# BLT_Preliminary_Avionics_Schematic_Brand.net
KiCad netlist of a schematic drawn in EAGLE
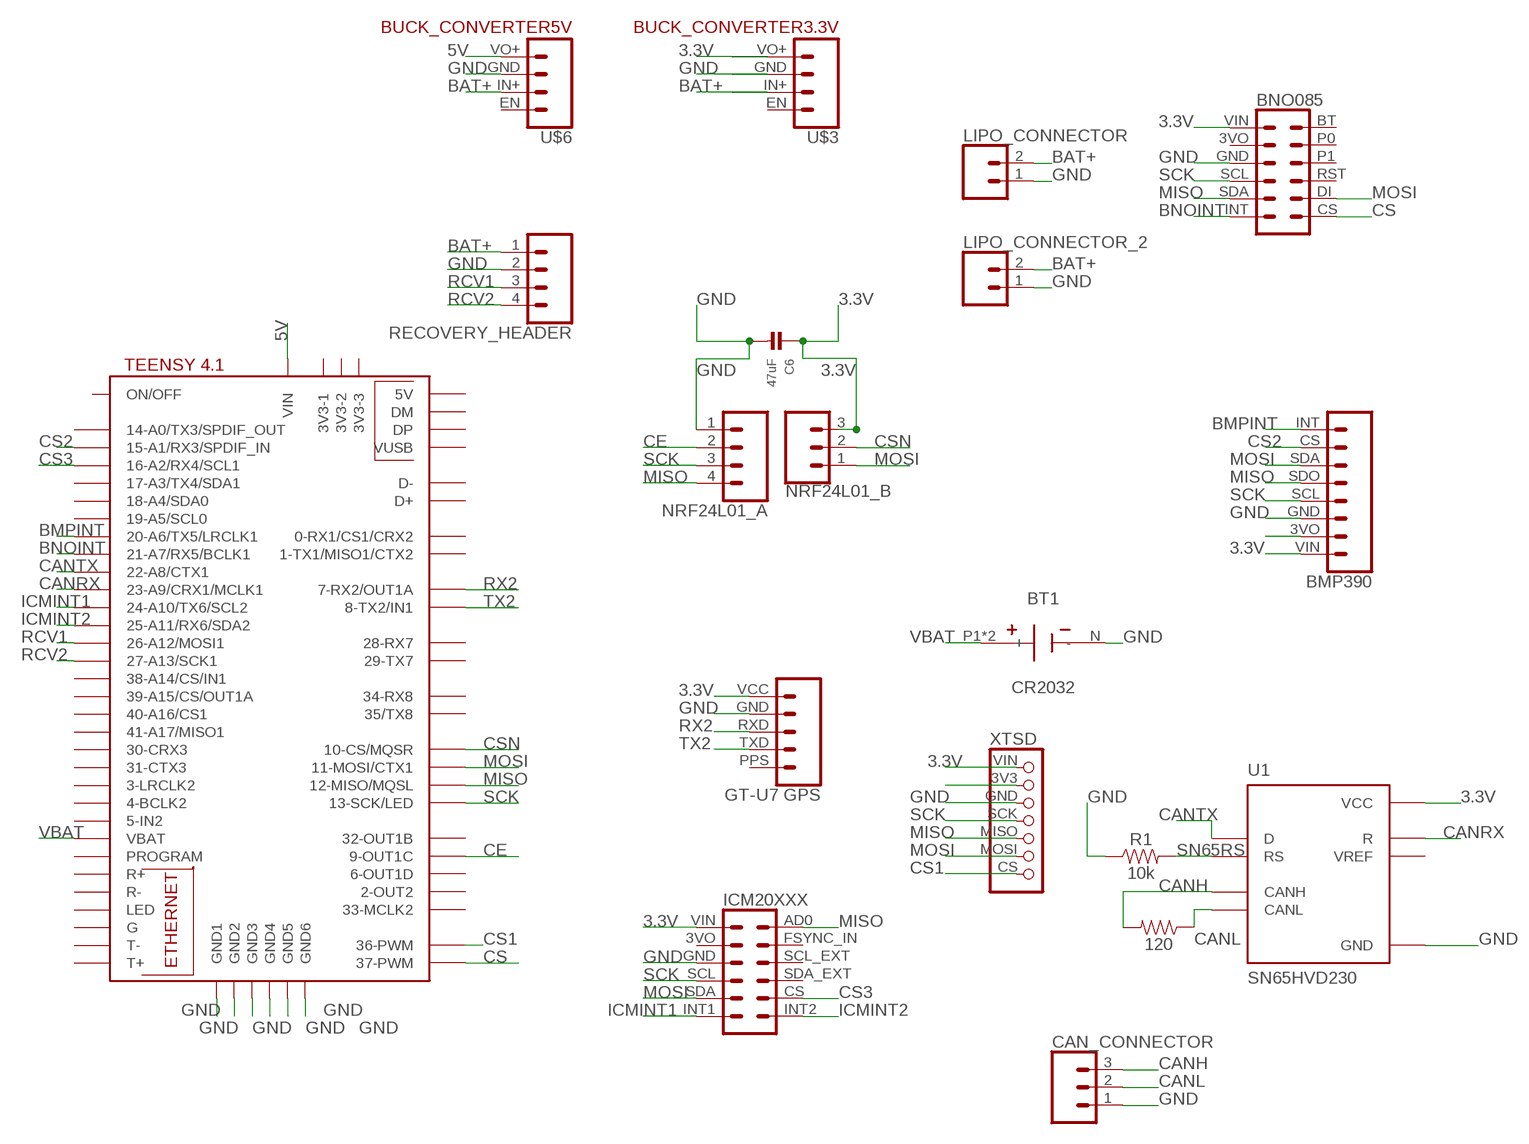
[diagram p0: schematic, sheet 1]

(export (version "E")
  (design (tool "Eeschema 10.0.6"))
  (components
    (comp (ref "120")
      (value "RESISTOR1206")
      (footprint "eagle-import:1206")
      (libsource (lib "eagle-import") (part "RESISTOR1206"))
    )
    (comp (ref "BT1")
      (value "CR2032")
      (footprint "eagle-import:BAT_3003")
      (fields (field (name "MANUFACTURER") "Keystone Electronics") (field (name "MPN") "3003"))
      (libsource (lib "eagle-import") (part "COIN-CELL-THM-3P?--3003CR2032"))
    )
    (comp (ref "C6")
      (value "47uF")
      (footprint "eagle-import:0805")
      (libsource (lib "eagle-import") (part "CAP_CERAMIC0805"))
    )
    (comp (ref "CAN_CONNECTOR")
      (value "CONN_03")
      (footprint "eagle-import:1X03")
      (libsource (lib "eagle-import") (part "CONN_03"))
    )
    (comp (ref "LIPO_CONNECTOR")
      (value "CONN_02PTH4")
      (footprint "eagle-import:1X02_XTRA_BIG")
      (libsource (lib "eagle-import") (part "CONN_02PTH4"))
    )
    (comp (ref "LIPO_CONNECTOR_2")
      (value "CONN_02")
      (footprint "eagle-import:1X02")
      (libsource (lib "eagle-import") (part "CONN_02"))
    )
    (comp (ref "NRF24L01_A")
      (value "CONN_04")
      (footprint "eagle-import:1X04")
      (libsource (lib "eagle-import") (part "CONN_04"))
    )
    (comp (ref "NRF24L01_B")
      (value "CONN_03")
      (footprint "eagle-import:1X03")
      (libsource (lib "eagle-import") (part "CONN_03"))
    )
    (comp (ref "R1")
      (value "10k")
      (footprint "eagle-import:0603")
      (libsource (lib "eagle-import") (part "10KOHM-0603-1/10W-1%"))
    )
    (comp (ref "RECOVERY_HEADER")
      (value "CONN_04")
      (footprint "eagle-import:1X04")
      (libsource (lib "eagle-import") (part "CONN_04"))
    )
    (comp (ref "U$1")
      (value "TEENSY41")
      (footprint "eagle-import:TEENSY41")
      (libsource (lib "eagle-import") (part "TEENSY41"))
    )
    (comp (ref "U$2")
      (value "BMP390")
      (footprint "eagle-import:MICROBUILDER_1X08_ROUND")
      (libsource (lib "eagle-import") (part "BMP390"))
    )
    (comp (ref "U$3")
      (value "BUCK_CONVERTER3.3V")
      (footprint "eagle-import:1X04")
      (fields (field (name "VOLTAGE") "3.3V"))
      (libsource (lib "eagle-import") (part "BUCK_CONVERTER3.3V"))
    )
    (comp (ref "U$4")
      (value "GT-U7_GPS")
      (footprint "eagle-import:1X05")
      (libsource (lib "eagle-import") (part "GT-U7_GPS"))
    )
    (comp (ref "U$5")
      (value "XTSDXTSD_PINS")
      (footprint "eagle-import:1X07")
      (libsource (lib "eagle-import") (part "XTSDXTSD_PINS"))
    )
    (comp (ref "U$6")
      (value "BUCK_CONVERTER5V")
      (footprint "eagle-import:1X04")
      (fields (field (name "VOLTAGE") "5V"))
      (libsource (lib "eagle-import") (part "BUCK_CONVERTER5V"))
    )
    (comp (ref "U$7")
      (value "BNO085")
      (footprint "eagle-import:MICROBUILDER_1X06_ROUND_70")
      (libsource (lib "eagle-import") (part "BNO085"))
    )
    (comp (ref "U$8")
      (value "ICM20XXX")
      (footprint "eagle-import:1X06")
      (libsource (lib "eagle-import") (part "ICM20XXX"))
    )
    (comp (ref "U1")
      (value "SN65HVD230")
      (footprint "eagle-import:SOIC127P599X175-8N")
      (fields (field (name "MF") "Texas Instruments"))
      (libsource (lib "eagle-import") (part "SN65HVD230"))
    )
  )
  (nets
    (net (code "1") (name "/3.3V") (class "Default")
      (node (ref "C6") (pin "1") (pinfunction "P$1_1") (pintype "passive"))
      (node (ref "NRF24L01_B") (pin "3") (pinfunction "3_3") (pintype "passive"))
      (node (ref "U$2") (pin "VIN") (pinfunction "VIN_VIN") (pintype "passive"))
      (node (ref "U$3") (pin "VO+") (pinfunction "VO+_VO+") (pintype "passive"))
      (node (ref "U$4") (pin "VCC") (pinfunction "VCC_VCC") (pintype "passive"))
      (node (ref "U$5") (pin "VIN") (pinfunction "VIN_VIN") (pintype "passive"))
      (node (ref "U$7") (pin "VIN") (pinfunction "VIN_VIN") (pintype "passive"))
      (node (ref "U$8") (pin "VIN") (pinfunction "VCC_VIN") (pintype "passive"))
      (node (ref "U1") (pin "3") (pinfunction "VCC_3") (pintype "power_in"))
    )
    (net (code "2") (name "/5V") (class "Default")
      (node (ref "U$1") (pin "VIN") (pinfunction "VIN_VIN") (pintype "bidirectional"))
      (node (ref "U$6") (pin "VO+") (pinfunction "VO+_VO+") (pintype "passive"))
    )
    (net (code "3") (name "/BAT+") (class "Default")
      (node (ref "LIPO_CONNECTOR") (pin "2") (pinfunction "2_2") (pintype "passive"))
      (node (ref "LIPO_CONNECTOR_2") (pin "2") (pinfunction "2_2") (pintype "passive"))
      (node (ref "RECOVERY_HEADER") (pin "1") (pinfunction "1_1") (pintype "passive"))
      (node (ref "U$3") (pin "IN+") (pinfunction "IN+_IN+") (pintype "passive"))
      (node (ref "U$6") (pin "IN+") (pinfunction "IN+_IN+") (pintype "passive"))
    )
    (net (code "4") (name "/BMPINT") (class "Default")
      (node (ref "U$1") (pin "20-A6/TX5/LRCLK1") (pinfunction "20-A6/TX5/LRCLK1_20-A6/TX5/LRCLK1") (pintype "bidirectional"))
      (node (ref "U$2") (pin "INT") (pinfunction "INT_INT") (pintype "passive"))
    )
    (net (code "5") (name "/BNOINT") (class "Default")
      (node (ref "U$1") (pin "21-A7/RX5/BCLK1") (pinfunction "21-A7/RX5/BCLK1_21-A7/RX5/BCLK1") (pintype "bidirectional"))
      (node (ref "U$7") (pin "INT") (pinfunction "INT_INT") (pintype "passive"))
    )
    (net (code "6") (name "/CANH") (class "Default")
      (node (ref "120") (pin "2") (pinfunction "2_2") (pintype "passive"))
      (node (ref "CAN_CONNECTOR") (pin "3") (pinfunction "3_3") (pintype "passive"))
      (node (ref "U1") (pin "7") (pinfunction "CANH_7") (pintype "bidirectional"))
    )
    (net (code "7") (name "/CANL") (class "Default")
      (node (ref "120") (pin "1") (pinfunction "1_1") (pintype "passive"))
      (node (ref "CAN_CONNECTOR") (pin "2") (pinfunction "2_2") (pintype "passive"))
      (node (ref "U1") (pin "6") (pinfunction "CANL_6") (pintype "bidirectional"))
    )
    (net (code "8") (name "/CANRX") (class "Default")
      (node (ref "U$1") (pin "23-A9/CRX1/MCLK1") (pinfunction "23-A9/CRX1/MCLK1_23-A9/CRX1/MCLK1") (pintype "bidirectional"))
      (node (ref "U1") (pin "4") (pinfunction "R_4") (pintype "output"))
    )
    (net (code "9") (name "/CANTX") (class "Default")
      (node (ref "U$1") (pin "22-A8/CTX1") (pinfunction "22-A8/CTX1_22-A8/CTX1") (pintype "bidirectional"))
      (node (ref "U1") (pin "1") (pinfunction "D_1") (pintype "input"))
    )
    (net (code "10") (name "/CE") (class "Default")
      (node (ref "NRF24L01_A") (pin "2") (pinfunction "2_2") (pintype "passive"))
      (node (ref "U$1") (pin "9-OUT1C") (pinfunction "9-OUT1C_9-OUT1C") (pintype "bidirectional"))
    )
    (net (code "11") (name "/CS") (class "Default")
      (node (ref "U$1") (pin "37-PWM") (pinfunction "37-PWM_37-PWM") (pintype "bidirectional"))
      (node (ref "U$7") (pin "CS") (pinfunction "CS_CS") (pintype "passive"))
    )
    (net (code "12") (name "/CS1") (class "Default")
      (node (ref "U$1") (pin "36-PWM") (pinfunction "36-PWM_36-PWM") (pintype "bidirectional"))
      (node (ref "U$5") (pin "CS") (pinfunction "CS_CS") (pintype "passive"))
    )
    (net (code "13") (name "/CS2") (class "Default")
      (node (ref "U$1") (pin "15-A1/RX3/SPDIF_IN") (pinfunction "15-A1/RX3/SPDIF_IN_15-A1/RX3/SPDIF_IN") (pintype "bidirectional"))
      (node (ref "U$2") (pin "CS") (pinfunction "CS_CS") (pintype "passive"))
    )
    (net (code "14") (name "/CS3") (class "Default")
      (node (ref "U$1") (pin "16-A2/RX4/SCL1") (pinfunction "16-A2/RX4/SCL1_16-A2/RX4/SCL1") (pintype "bidirectional"))
      (node (ref "U$8") (pin "CS") (pinfunction "CS_CS") (pintype "passive"))
    )
    (net (code "15") (name "/CSN") (class "Default")
      (node (ref "NRF24L01_B") (pin "2") (pinfunction "2_2") (pintype "passive"))
      (node (ref "U$1") (pin "10-CS\\MQSR") (pinfunction "10-CS/MQSR_10-CS\\MQSR") (pintype "bidirectional"))
    )
    (net (code "16") (name "/GND") (class "Default")
      (node (ref "BT1") (pin "N") (pinfunction "-_N") (pintype "bidirectional"))
      (node (ref "C6") (pin "2") (pinfunction "P$2_2") (pintype "passive"))
      (node (ref "CAN_CONNECTOR") (pin "1") (pinfunction "1_1") (pintype "passive"))
      (node (ref "LIPO_CONNECTOR") (pin "1") (pinfunction "1_1") (pintype "passive"))
      (node (ref "LIPO_CONNECTOR_2") (pin "1") (pinfunction "1_1") (pintype "passive"))
      (node (ref "NRF24L01_A") (pin "1") (pinfunction "1_1") (pintype "passive"))
      (node (ref "R1") (pin "1") (pinfunction "1_1") (pintype "passive"))
      (node (ref "RECOVERY_HEADER") (pin "2") (pinfunction "2_2") (pintype "passive"))
      (node (ref "U$1") (pin "GND1") (pinfunction "GND1_GND1") (pintype "bidirectional"))
      (node (ref "U$1") (pin "GND2") (pinfunction "GND2_GND2") (pintype "bidirectional"))
      (node (ref "U$1") (pin "GND3") (pinfunction "GND3_GND3") (pintype "bidirectional"))
      (node (ref "U$1") (pin "GND4") (pinfunction "GND4_GND4") (pintype "bidirectional"))
      (node (ref "U$1") (pin "GND5") (pinfunction "GND5_GND5") (pintype "bidirectional"))
      (node (ref "U$1") (pin "GND6") (pinfunction "GND6_GND6") (pintype "bidirectional"))
      (node (ref "U$2") (pin "GND") (pinfunction "GND_GND") (pintype "passive"))
      (node (ref "U$3") (pin "GND") (pinfunction "GND_GND") (pintype "passive"))
      (node (ref "U$4") (pin "GND") (pinfunction "GND_GND") (pintype "passive"))
      (node (ref "U$5") (pin "GND") (pinfunction "GND_GND") (pintype "passive"))
      (node (ref "U$6") (pin "GND") (pinfunction "GND_GND") (pintype "passive"))
      (node (ref "U$7") (pin "GND") (pinfunction "GND_GND") (pintype "passive"))
      (node (ref "U$8") (pin "GND") (pinfunction "GND_GND") (pintype "passive"))
      (node (ref "U1") (pin "2") (pinfunction "GND_2") (pintype "power_in"))
    )
    (net (code "17") (name "/ICMINT1") (class "Default")
      (node (ref "U$1") (pin "24-A10/TX6/SCL2") (pinfunction "24-A10/TX6/SCL2_24-A10/TX6/SCL2") (pintype "bidirectional"))
      (node (ref "U$8") (pin "INT1") (pinfunction "INT1_INT1") (pintype "passive"))
    )
    (net (code "18") (name "/ICMINT2") (class "Default")
      (node (ref "U$1") (pin "25-A11/RX6/SDA2") (pinfunction "25-A11/RX6/SDA2_25-A11/RX6/SDA2") (pintype "bidirectional"))
      (node (ref "U$8") (pin "INT2") (pinfunction "INT2_INT2") (pintype "passive"))
    )
    (net (code "19") (name "/MISO") (class "Default")
      (node (ref "NRF24L01_A") (pin "4") (pinfunction "4_4") (pintype "passive"))
      (node (ref "U$1") (pin "12-MISO/MQSL") (pinfunction "12-MISO/MQSL_12-MISO/MQSL") (pintype "bidirectional"))
      (node (ref "U$2") (pin "SDO") (pinfunction "SDO_SDO") (pintype "passive"))
      (node (ref "U$5") (pin "MISO") (pinfunction "MISO_MISO") (pintype "passive"))
      (node (ref "U$7") (pin "SDA") (pinfunction "SDA_SDA") (pintype "passive"))
      (node (ref "U$8") (pin "AD0") (pinfunction "AD0_AD0") (pintype "passive"))
    )
    (net (code "20") (name "/MOSI") (class "Default")
      (node (ref "NRF24L01_B") (pin "1") (pinfunction "1_1") (pintype "passive"))
      (node (ref "U$1") (pin "11-MOSI/CTX1") (pinfunction "11-MOSI/CTX1_11-MOSI/CTX1") (pintype "bidirectional"))
      (node (ref "U$2") (pin "SDA") (pinfunction "SDA_SDA") (pintype "passive"))
      (node (ref "U$5") (pin "MOSI") (pinfunction "MOSI_MOSI") (pintype "passive"))
      (node (ref "U$7") (pin "DI") (pinfunction "DI_DI") (pintype "passive"))
      (node (ref "U$8") (pin "SDA") (pinfunction "SDA_SDA") (pintype "passive"))
    )
    (net (code "21") (name "/RCV1") (class "Default")
      (node (ref "RECOVERY_HEADER") (pin "3") (pinfunction "3_3") (pintype "passive"))
      (node (ref "U$1") (pin "26-A12/MOSI1") (pinfunction "26-A12/MOSI1_26-A12/MOSI1") (pintype "bidirectional"))
    )
    (net (code "22") (name "/RCV2") (class "Default")
      (node (ref "RECOVERY_HEADER") (pin "4") (pinfunction "4_4") (pintype "passive"))
      (node (ref "U$1") (pin "27-A13/SCK1") (pinfunction "27-A13/SCK1_27-A13/SCK1") (pintype "bidirectional"))
    )
    (net (code "23") (name "/RX2") (class "Default")
      (node (ref "U$1") (pin "7-RX2/OUT1A") (pinfunction "7-RX2/OUT1A_7-RX2/OUT1A") (pintype "bidirectional"))
      (node (ref "U$4") (pin "RXD") (pinfunction "RXD_RXD") (pintype "passive"))
    )
    (net (code "24") (name "/SCK") (class "Default")
      (node (ref "NRF24L01_A") (pin "3") (pinfunction "3_3") (pintype "passive"))
      (node (ref "U$1") (pin "13-SCK/LED") (pinfunction "13-SCK/LED_13-SCK/LED") (pintype "bidirectional"))
      (node (ref "U$2") (pin "SCL") (pinfunction "SCL_SCL") (pintype "passive"))
      (node (ref "U$5") (pin "SCK") (pinfunction "SCK_SCK") (pintype "passive"))
      (node (ref "U$7") (pin "SCL") (pinfunction "SCL_SCL") (pintype "passive"))
      (node (ref "U$8") (pin "SCL") (pinfunction "SCL_SCL") (pintype "passive"))
    )
    (net (code "25") (name "/SN65RS") (class "Default")
      (node (ref "R1") (pin "2") (pinfunction "2_2") (pintype "passive"))
      (node (ref "U1") (pin "8") (pinfunction "RS_8") (pintype "input"))
    )
    (net (code "26") (name "/TX2") (class "Default")
      (node (ref "U$1") (pin "8-TX2/IN1") (pinfunction "8-TX2/IN1_8-TX2/IN1") (pintype "bidirectional"))
      (node (ref "U$4") (pin "TXD") (pinfunction "TXD_TXD") (pintype "passive"))
    )
    (net (code "27") (name "/VBAT") (class "Default")
      (node (ref "BT1") (pin "P1") (pinfunction "+_P1") (pintype "bidirectional"))
      (node (ref "BT1") (pin "P2") (pinfunction "+_P2") (pintype "bidirectional"))
      (node (ref "U$1") (pin "VBAT") (pinfunction "VBAT_VBAT") (pintype "bidirectional"))
    )
    (net (code "28") (name "unconnected-(U$1-5V-Pad+5V)") (class "Default")
      (node (ref "U$1") (pin "+5V") (pinfunction "5V_+5V") (pintype "bidirectional"))
    )
    (net (code "29") (name "unconnected-(U$1-35{slash}TX8-Pad35-TX8)") (class "Default")
      (node (ref "U$1") (pin "35-TX8") (pinfunction "35/TX8_35-TX8") (pintype "bidirectional"))
    )
    (net (code "30") (name "unconnected-(U$1-Pad0-RX1{slash}CS1{slash}CRX2)") (class "Default")
      (node (ref "U$1") (pin "0-RX1/CS1/CRX2") (pinfunction "0-RX1/CS1/CRX2_0-RX1/CS1/CRX2") (pintype "bidirectional"))
    )
    (net (code "31") (name "unconnected-(U$1-Pad1-TX1{slash}MISO1{slash}CTX2)") (class "Default")
      (node (ref "U$1") (pin "1-TX1/MISO1/CTX2") (pinfunction "1-TX1/MISO1/CTX2_1-TX1/MISO1/CTX2") (pintype "bidirectional"))
    )
    (net (code "32") (name "unconnected-(U$1-Pad2-OUT2)") (class "Default")
      (node (ref "U$1") (pin "2-OUT2") (pinfunction "2-OUT2_2-OUT2") (pintype "bidirectional"))
    )
    (net (code "33") (name "unconnected-(U$1-Pad3-LRCLK2)") (class "Default")
      (node (ref "U$1") (pin "3-LRCLK2") (pinfunction "3-LRCLK2_3-LRCLK2") (pintype "bidirectional"))
    )
    (net (code "34") (name "unconnected-(U$1-Pad3V3-1)") (class "Default")
      (node (ref "U$1") (pin "3V3-1") (pinfunction "3V3-1_3V3-1") (pintype "bidirectional"))
    )
    (net (code "35") (name "unconnected-(U$1-Pad3V3-2)") (class "Default")
      (node (ref "U$1") (pin "3V3-2") (pinfunction "3V3-2_3V3-2") (pintype "bidirectional"))
    )
    (net (code "36") (name "unconnected-(U$1-Pad3V3-3)") (class "Default")
      (node (ref "U$1") (pin "3V3-3") (pinfunction "3V3-3_3V3-3") (pintype "bidirectional"))
    )
    (net (code "37") (name "unconnected-(U$1-Pad4-BCLK2)") (class "Default")
      (node (ref "U$1") (pin "4-BCLK2") (pinfunction "4-BCLK2_4-BCLK2") (pintype "bidirectional"))
    )
    (net (code "38") (name "unconnected-(U$1-Pad5-IN2)") (class "Default")
      (node (ref "U$1") (pin "5-IN2") (pinfunction "5-IN2_5-IN2") (pintype "bidirectional"))
    )
    (net (code "39") (name "unconnected-(U$1-Pad6-OUT1D)") (class "Default")
      (node (ref "U$1") (pin "6-OUT1D") (pinfunction "6-OUT1D_6-OUT1D") (pintype "bidirectional"))
    )
    (net (code "40") (name "unconnected-(U$1-Pad14-A0{slash}TX3{slash}SPDIF_OUT)") (class "Default")
      (node (ref "U$1") (pin "14-A0/TX3/SPDIF_OUT") (pinfunction "14-A0/TX3/SPDIF_OUT_14-A0/TX3/SPDIF_OUT") (pintype "bidirectional"))
    )
    (net (code "41") (name "unconnected-(U$1-Pad17-A3{slash}TX4{slash}SDA1)") (class "Default")
      (node (ref "U$1") (pin "17-A3/TX4/SDA1") (pinfunction "17-A3/TX4/SDA1_17-A3/TX4/SDA1") (pintype "bidirectional"))
    )
    (net (code "42") (name "unconnected-(U$1-Pad18-A4{slash}SDA0)") (class "Default")
      (node (ref "U$1") (pin "18-A4/SDA0") (pinfunction "18-A4/SDA0_18-A4/SDA0") (pintype "bidirectional"))
    )
    (net (code "43") (name "unconnected-(U$1-Pad19-A5{slash}SCL0)") (class "Default")
      (node (ref "U$1") (pin "19-A5/SCL0") (pinfunction "19-A5/SCL0_19-A5/SCL0") (pintype "bidirectional"))
    )
    (net (code "44") (name "unconnected-(U$1-Pad28-RX7)") (class "Default")
      (node (ref "U$1") (pin "28-RX7") (pinfunction "28-RX7_28-RX7") (pintype "bidirectional"))
    )
    (net (code "45") (name "unconnected-(U$1-Pad29-TX7)") (class "Default")
      (node (ref "U$1") (pin "29-TX7") (pinfunction "29-TX7_29-TX7") (pintype "bidirectional"))
    )
    (net (code "46") (name "unconnected-(U$1-Pad30-CRX3)") (class "Default")
      (node (ref "U$1") (pin "30-CRX3") (pinfunction "30-CRX3_30-CRX3") (pintype "bidirectional"))
    )
    (net (code "47") (name "unconnected-(U$1-Pad31-CTX3)") (class "Default")
      (node (ref "U$1") (pin "31-CTX3") (pinfunction "31-CTX3_31-CTX3") (pintype "bidirectional"))
    )
    (net (code "48") (name "unconnected-(U$1-Pad32-OUT1B)") (class "Default")
      (node (ref "U$1") (pin "32-OUT1B") (pinfunction "32-OUT1B_32-OUT1B") (pintype "bidirectional"))
    )
    (net (code "49") (name "unconnected-(U$1-Pad33-MCLK2)") (class "Default")
      (node (ref "U$1") (pin "33-MCLK2") (pinfunction "33-MCLK2_33-MCLK2") (pintype "bidirectional"))
    )
    (net (code "50") (name "unconnected-(U$1-Pad34-RX8)") (class "Default")
      (node (ref "U$1") (pin "34-RX8") (pinfunction "34-RX8_34-RX8") (pintype "bidirectional"))
    )
    (net (code "51") (name "unconnected-(U$1-Pad38-A14{slash}CS{slash}IN1)") (class "Default")
      (node (ref "U$1") (pin "38-A14/CS/IN1") (pinfunction "38-A14/CS/IN1_38-A14/CS/IN1") (pintype "bidirectional"))
    )
    (net (code "52") (name "unconnected-(U$1-Pad39-A15{slash}CS{slash}OUT1A)") (class "Default")
      (node (ref "U$1") (pin "39-A15/CS/OUT1A") (pinfunction "39-A15/CS/OUT1A_39-A15/CS/OUT1A") (pintype "bidirectional"))
    )
    (net (code "53") (name "unconnected-(U$1-Pad40-A16{slash}CS1)") (class "Default")
      (node (ref "U$1") (pin "40-A16/CS1") (pinfunction "40-A16/CS1_40-A16/CS1") (pintype "bidirectional"))
    )
    (net (code "54") (name "unconnected-(U$1-Pad41-A17{slash}MISO1)") (class "Default")
      (node (ref "U$1") (pin "41-A17/MISO1") (pinfunction "41-A17/MISO1_41-A17/MISO1") (pintype "bidirectional"))
    )
    (net (code "55") (name "unconnected-(U$1-PadD+)") (class "Default")
      (node (ref "U$1") (pin "D+") (pinfunction "D+_D+") (pintype "bidirectional"))
    )
    (net (code "56") (name "unconnected-(U$1-PadD-)") (class "Default")
      (node (ref "U$1") (pin "D-") (pinfunction "D-_D-") (pintype "bidirectional"))
    )
    (net (code "57") (name "unconnected-(U$1-PadDM)") (class "Default")
      (node (ref "U$1") (pin "DM") (pinfunction "DM_DM") (pintype "bidirectional"))
    )
    (net (code "58") (name "unconnected-(U$1-PadDP)") (class "Default")
      (node (ref "U$1") (pin "DP") (pinfunction "DP_DP") (pintype "bidirectional"))
    )
    (net (code "59") (name "unconnected-(U$1-PadG)") (class "Default")
      (node (ref "U$1") (pin "G") (pinfunction "G_G") (pintype "bidirectional"))
    )
    (net (code "60") (name "unconnected-(U$1-PadLED)") (class "Default")
      (node (ref "U$1") (pin "LED") (pinfunction "LED_LED") (pintype "bidirectional"))
    )
    (net (code "61") (name "unconnected-(U$1-PadON{slash}OFF)") (class "Default")
      (node (ref "U$1") (pin "ON/OFF") (pinfunction "ON/OFF_ON/OFF") (pintype "bidirectional"))
    )
    (net (code "62") (name "unconnected-(U$1-PadPROGRAM)") (class "Default")
      (node (ref "U$1") (pin "PROGRAM") (pinfunction "PROGRAM_PROGRAM") (pintype "bidirectional"))
    )
    (net (code "63") (name "unconnected-(U$1-PadR+)") (class "Default")
      (node (ref "U$1") (pin "R+") (pinfunction "R+_R+") (pintype "bidirectional"))
    )
    (net (code "64") (name "unconnected-(U$1-PadR-)") (class "Default")
      (node (ref "U$1") (pin "R-") (pinfunction "R-_R-") (pintype "bidirectional"))
    )
    (net (code "65") (name "unconnected-(U$1-PadT+)") (class "Default")
      (node (ref "U$1") (pin "T+") (pinfunction "T+_T+") (pintype "bidirectional"))
    )
    (net (code "66") (name "unconnected-(U$1-PadT-)") (class "Default")
      (node (ref "U$1") (pin "T-") (pinfunction "T-_T-") (pintype "bidirectional"))
    )
    (net (code "67") (name "unconnected-(U$1-PadVUSB)") (class "Default")
      (node (ref "U$1") (pin "VUSB") (pinfunction "VUSB_VUSB") (pintype "bidirectional"))
    )
    (net (code "68") (name "unconnected-(U$2-Pad3VO)") (class "Default")
      (node (ref "U$2") (pin "3VO") (pinfunction "3VO_3VO") (pintype "passive"))
    )
    (net (code "69") (name "unconnected-(U$3-PadEN)") (class "Default")
      (node (ref "U$3") (pin "EN") (pinfunction "EN_EN") (pintype "passive"))
    )
    (net (code "70") (name "unconnected-(U$4-PadPPS)") (class "Default")
      (node (ref "U$4") (pin "PPS") (pinfunction "PPS_PPS") (pintype "passive"))
    )
    (net (code "71") (name "unconnected-(U$5-Pad3V3)") (class "Default")
      (node (ref "U$5") (pin "3V3") (pinfunction "3V3_3V3") (pintype "passive"))
    )
    (net (code "72") (name "unconnected-(U$6-PadEN)") (class "Default")
      (node (ref "U$6") (pin "EN") (pinfunction "EN_EN") (pintype "passive"))
    )
    (net (code "73") (name "unconnected-(U$7-Pad3VO)") (class "Default")
      (node (ref "U$7") (pin "3VO") (pinfunction "3VO_3VO") (pintype "passive"))
    )
    (net (code "74") (name "unconnected-(U$7-PadBT)") (class "Default")
      (node (ref "U$7") (pin "BT") (pinfunction "BT_BT") (pintype "passive"))
    )
    (net (code "75") (name "unconnected-(U$7-PadP0)") (class "Default")
      (node (ref "U$7") (pin "P0") (pinfunction "P0_P0") (pintype "passive"))
    )
    (net (code "76") (name "unconnected-(U$7-PadP1)") (class "Default")
      (node (ref "U$7") (pin "P1") (pinfunction "P1_P1") (pintype "passive"))
    )
    (net (code "77") (name "unconnected-(U$7-PadRST)") (class "Default")
      (node (ref "U$7") (pin "RST") (pinfunction "RST_RST") (pintype "passive"))
    )
    (net (code "78") (name "unconnected-(U$8-Pad3VO)") (class "Default")
      (node (ref "U$8") (pin "3VO") (pinfunction "3VO_3VO") (pintype "passive"))
    )
    (net (code "79") (name "unconnected-(U$8-PadFSYNC_IN)") (class "Default")
      (node (ref "U$8") (pin "FSYNC_IN") (pinfunction "FSYNC_IN_FSYNC_IN") (pintype "passive"))
    )
    (net (code "80") (name "unconnected-(U$8-PadSCL_EXT)") (class "Default")
      (node (ref "U$8") (pin "SCL_EXT") (pinfunction "SCL_EXT_SCL_EXT") (pintype "passive"))
    )
    (net (code "81") (name "unconnected-(U$8-PadSDA_EXT)") (class "Default")
      (node (ref "U$8") (pin "SDA_EXT") (pinfunction "SDA_EXT_SDA_EXT") (pintype "passive"))
    )
    (net (code "82") (name "unconnected-(U1-VREF-Pad5)") (class "Default")
      (node (ref "U1") (pin "5") (pinfunction "VREF_5") (pintype "output"))
    )
  )
)
